# Arduino.net
KiCad netlist of a schematic drawn in Altium Designer
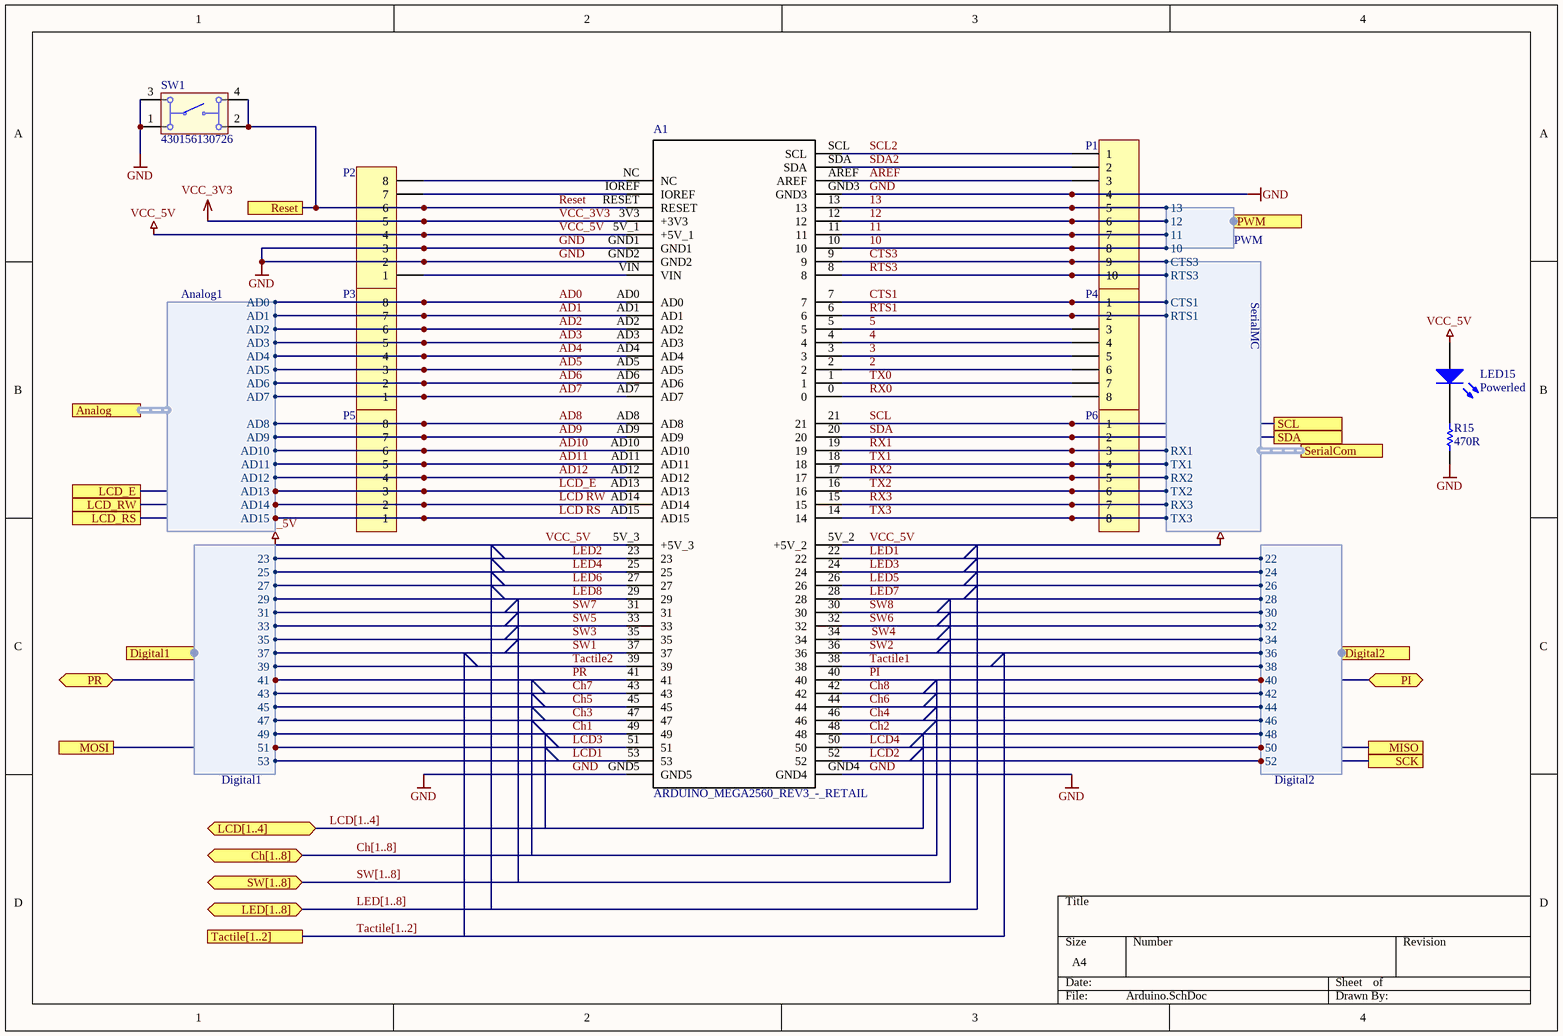
[diagram p0: Arduino.SchDoc]

(export (version "E")
  (design (tool "Eeschema 10.0.6"))
  (components
    (comp (ref "A1")
      (value "ARDUINO_MEGA2560_REV3_-_RETAIL")
      (footprint "*ARDUINO_MEGA2560_REV3_-_RETAIL_ARDUINO_MEGA2560_REV3_-_RETAIL(Primary)")
      (description "Dev.kit: Arduino; SPI, TWI, UART; ICSP, USB B, pin strips, supply")
      (fields (field (name "MF") "Arduino") (field (name "MP") "ARDUINO MEGA2560 REV3 - RETAIL"))
      (libsource (lib "ARDUINO_MEGA2560_REV3_-_RETAIL") (part "ARDUINO_MEGA2560_REV3_-_RETAIL"))
    )
    (comp (ref "LED15")
      (value "Powerled")
      (footprint "1206_A")
      (description "SMD mono-color Chip LED, WL-SMCW, Red")
      (fields (field (name "PARTNUMBER") "150120RS75000") (field (name "MANUFACTURER") "Wuerth Elektronik"))
      (libsource (lib "Altium Content Vault") (part "WE-LED_K1A2-2"))
    )
    (comp (ref "P1")
      (value "Header 10")
      (footprint "HDR1X10")
      (description "Header, 10-Pin")
      (fields (field (name "PUBLISHER") "Altium Limited"))
      (libsource (lib "Miscellaneous Connectors") (part "Header 10"))
    )
    (comp (ref "P2")
      (value "Header 8")
      (footprint "HDR1X8")
      (description "Header, 8-Pin")
      (fields (field (name "PUBLISHER") "Altium Limited"))
      (libsource (lib "") (part "Header 8_1"))
    )
    (comp (ref "P3")
      (value "Header 8")
      (footprint "HDR1X8")
      (description "Header, 8-Pin")
      (fields (field (name "PUBLISHER") "Altium Limited"))
      (libsource (lib "") (part "Header 8_1"))
    )
    (comp (ref "P4")
      (value "Header 8")
      (footprint "HDR1X8")
      (description "Header, 8-Pin")
      (fields (field (name "PUBLISHER") "Altium Limited"))
      (libsource (lib "Miscellaneous Connectors") (part "Header 8"))
    )
    (comp (ref "P5")
      (value "Header 8")
      (footprint "HDR1X8")
      (description "Header, 8-Pin")
      (fields (field (name "PUBLISHER") "Altium Limited"))
      (libsource (lib "") (part "Header 8_1"))
    )
    (comp (ref "P6")
      (value "Header 8")
      (footprint "HDR1X8")
      (description "Header, 8-Pin")
      (fields (field (name "PUBLISHER") "Altium Limited"))
      (libsource (lib "Miscellaneous Connectors") (part "Header 8"))
    )
    (comp (ref "R15")
      (value "470R")
      (footprint "RESC0805(2012)_M")
      (description "470R 0.125W 1% 0805 (2012 Metric)  SMD")
      (fields (field (name "POWER") "0.125 W") (field (name "TOLERANCE") "1 %"))
      (libsource (lib "Altium Content Vault") (part "RES"))
    )
    (comp (ref "SW1")
      (value "430156130726")
      (footprint "430156130726")
      (description "WS-TATV THT Tact Switch 6X6 mm")
      (fields (field (name "MANUFACTURER") "Wuerth Elektronik"))
      (libsource (lib "Altium Content Vault") (part "WE-TACT-SW-4"))
    )
  )
  (nets
    (net (code "6") (name "/2") (class "Default")
      (node (ref "A1") (pin "2") (pinfunction "2_2") (pintype "passive"))
      (node (ref "P4") (pin "6") (pinfunction "6_6") (pintype "passive"))
    )
    (net (code "7") (name "/3") (class "Default")
      (node (ref "A1") (pin "3") (pinfunction "3_3") (pintype "passive"))
      (node (ref "P4") (pin "5") (pinfunction "5_5") (pintype "passive"))
    )
    (net (code "8") (name "/4") (class "Default")
      (node (ref "A1") (pin "4") (pinfunction "4_4") (pintype "passive"))
      (node (ref "P4") (pin "4") (pinfunction "4_4") (pintype "passive"))
    )
    (net (code "9") (name "/5") (class "Default")
      (node (ref "A1") (pin "5") (pinfunction "5_5") (pintype "passive"))
      (node (ref "P4") (pin "3") (pinfunction "3_3") (pintype "passive"))
    )
    (net (code "10") (name "/10") (class "Default")
      (node (ref "A1") (pin "10") (pinfunction "10_10") (pintype "passive"))
      (node (ref "P1") (pin "8") (pinfunction "8_8") (pintype "passive"))
    )
    (net (code "11") (name "/11") (class "Default")
      (node (ref "A1") (pin "11") (pinfunction "11_11") (pintype "passive"))
      (node (ref "P1") (pin "7") (pinfunction "7_7") (pintype "passive"))
    )
    (net (code "12") (name "/12") (class "Default")
      (node (ref "A1") (pin "12") (pinfunction "12_12") (pintype "passive"))
      (node (ref "P1") (pin "6") (pinfunction "6_6") (pintype "passive"))
    )
    (net (code "13") (name "/13") (class "Default")
      (node (ref "A1") (pin "13") (pinfunction "13_13") (pintype "passive"))
      (node (ref "P1") (pin "5") (pinfunction "5_5") (pintype "passive"))
    )
    (net (code "14") (name "/AD0") (class "Default")
      (node (ref "A1") (pin "AD0") (pinfunction "AD0_AD0") (pintype "passive"))
      (node (ref "P3") (pin "8") (pinfunction "8_8") (pintype "passive"))
    )
    (net (code "15") (name "/AD1") (class "Default")
      (node (ref "A1") (pin "AD1") (pinfunction "AD1_AD1") (pintype "passive"))
      (node (ref "P3") (pin "7") (pinfunction "7_7") (pintype "passive"))
    )
    (net (code "16") (name "/AD2") (class "Default")
      (node (ref "A1") (pin "AD2") (pinfunction "AD2_AD2") (pintype "passive"))
      (node (ref "P3") (pin "6") (pinfunction "6_6") (pintype "passive"))
    )
    (net (code "17") (name "/AD3") (class "Default")
      (node (ref "A1") (pin "AD3") (pinfunction "AD3_AD3") (pintype "passive"))
      (node (ref "P3") (pin "5") (pinfunction "5_5") (pintype "passive"))
    )
    (net (code "18") (name "/AD4") (class "Default")
      (node (ref "A1") (pin "AD4") (pinfunction "AD4_AD4") (pintype "passive"))
      (node (ref "P3") (pin "4") (pinfunction "4_4") (pintype "passive"))
    )
    (net (code "19") (name "/AD5") (class "Default")
      (node (ref "A1") (pin "AD5") (pinfunction "AD5_AD5") (pintype "passive"))
      (node (ref "P3") (pin "3") (pinfunction "3_3") (pintype "passive"))
    )
    (net (code "20") (name "/AD6") (class "Default")
      (node (ref "A1") (pin "AD6") (pinfunction "AD6_AD6") (pintype "passive"))
      (node (ref "P3") (pin "2") (pinfunction "2_2") (pintype "passive"))
    )
    (net (code "21") (name "/AD7") (class "Default")
      (node (ref "A1") (pin "AD7") (pinfunction "AD7_AD7") (pintype "passive"))
      (node (ref "P3") (pin "1") (pinfunction "1_1") (pintype "passive"))
    )
    (net (code "22") (name "/AD8") (class "Default")
      (node (ref "A1") (pin "AD8") (pinfunction "AD8_AD8") (pintype "passive"))
      (node (ref "P5") (pin "8") (pinfunction "8_8") (pintype "passive"))
    )
    (net (code "23") (name "/AD9") (class "Default")
      (node (ref "A1") (pin "AD9") (pinfunction "AD9_AD9") (pintype "passive"))
      (node (ref "P5") (pin "7") (pinfunction "7_7") (pintype "passive"))
    )
    (net (code "24") (name "/AD10") (class "Default")
      (node (ref "A1") (pin "AD10") (pinfunction "AD10_AD10") (pintype "passive"))
      (node (ref "P5") (pin "6") (pinfunction "6_6") (pintype "passive"))
    )
    (net (code "25") (name "/AD11") (class "Default")
      (node (ref "A1") (pin "AD11") (pinfunction "AD11_AD11") (pintype "passive"))
      (node (ref "P5") (pin "5") (pinfunction "5_5") (pintype "passive"))
    )
    (net (code "26") (name "/AD12") (class "Default")
      (node (ref "A1") (pin "AD12") (pinfunction "AD12_AD12") (pintype "passive"))
      (node (ref "P5") (pin "4") (pinfunction "4_4") (pintype "passive"))
    )
    (net (code "27") (name "/AREF") (class "Default")
      (node (ref "A1") (pin "AREF") (pinfunction "AREF_AREF") (pintype "passive"))
      (node (ref "P1") (pin "3") (pinfunction "3_3") (pintype "passive"))
    )
    (net (code "28") (name "/CTS1") (class "Default")
      (node (ref "A1") (pin "7") (pinfunction "7_7") (pintype "passive"))
      (node (ref "P4") (pin "1") (pinfunction "1_1") (pintype "passive"))
    )
    (net (code "29") (name "/CTS3") (class "Default")
      (node (ref "A1") (pin "9") (pinfunction "9_9") (pintype "passive"))
      (node (ref "P1") (pin "9") (pinfunction "9_9") (pintype "passive"))
    )
    (net (code "30") (name "/Ch1") (class "Default")
      (node (ref "A1") (pin "49") (pinfunction "49_49") (pintype "passive"))
    )
    (net (code "31") (name "/Ch2") (class "Default")
      (node (ref "A1") (pin "48") (pinfunction "48_48") (pintype "passive"))
    )
    (net (code "32") (name "/Ch3") (class "Default")
      (node (ref "A1") (pin "47") (pinfunction "47_47") (pintype "passive"))
    )
    (net (code "33") (name "/Ch4") (class "Default")
      (node (ref "A1") (pin "46") (pinfunction "46_46") (pintype "passive"))
    )
    (net (code "34") (name "/Ch5") (class "Default")
      (node (ref "A1") (pin "45") (pinfunction "45_45") (pintype "passive"))
    )
    (net (code "35") (name "/Ch6") (class "Default")
      (node (ref "A1") (pin "44") (pinfunction "44_44") (pintype "passive"))
    )
    (net (code "36") (name "/Ch7") (class "Default")
      (node (ref "A1") (pin "43") (pinfunction "43_43") (pintype "passive"))
    )
    (net (code "37") (name "/Ch8") (class "Default")
      (node (ref "A1") (pin "42") (pinfunction "42_42") (pintype "passive"))
    )
    (net (code "39") (name "/LCD RS") (class "Default")
      (node (ref "A1") (pin "AD15") (pinfunction "AD15_AD15") (pintype "passive"))
      (node (ref "P5") (pin "1") (pinfunction "1_1") (pintype "passive"))
    )
    (net (code "40") (name "/LCD RW") (class "Default")
      (node (ref "A1") (pin "AD14") (pinfunction "AD14_AD14") (pintype "passive"))
      (node (ref "P5") (pin "2") (pinfunction "2_2") (pintype "passive"))
    )
    (net (code "41") (name "/LCD1") (class "Default")
      (node (ref "A1") (pin "53") (pinfunction "53_53") (pintype "passive"))
    )
    (net (code "42") (name "/LCD2") (class "Default")
      (node (ref "A1") (pin "52") (pinfunction "52_52") (pintype "passive"))
    )
    (net (code "43") (name "/LCD3") (class "Default")
      (node (ref "A1") (pin "51") (pinfunction "51_51") (pintype "passive"))
    )
    (net (code "44") (name "/LCD4") (class "Default")
      (node (ref "A1") (pin "50") (pinfunction "50_50") (pintype "passive"))
    )
    (net (code "46") (name "/LCD_E") (class "Default")
      (node (ref "A1") (pin "AD13") (pinfunction "AD13_AD13") (pintype "passive"))
      (node (ref "P5") (pin "3") (pinfunction "3_3") (pintype "passive"))
    )
    (net (code "47") (name "/LED1") (class "Default")
      (node (ref "A1") (pin "22") (pinfunction "22_22") (pintype "passive"))
    )
    (net (code "48") (name "/LED2") (class "Default")
      (node (ref "A1") (pin "23") (pinfunction "23_23") (pintype "passive"))
    )
    (net (code "49") (name "/LED3") (class "Default")
      (node (ref "A1") (pin "24") (pinfunction "24_24") (pintype "passive"))
    )
    (net (code "50") (name "/LED4") (class "Default")
      (node (ref "A1") (pin "25") (pinfunction "25_25") (pintype "passive"))
    )
    (net (code "51") (name "/LED5") (class "Default")
      (node (ref "A1") (pin "26") (pinfunction "26_26") (pintype "passive"))
    )
    (net (code "52") (name "/LED6") (class "Default")
      (node (ref "A1") (pin "27") (pinfunction "27_27") (pintype "passive"))
    )
    (net (code "53") (name "/LED7") (class "Default")
      (node (ref "A1") (pin "28") (pinfunction "28_28") (pintype "passive"))
    )
    (net (code "54") (name "/LED8") (class "Default")
      (node (ref "A1") (pin "29") (pinfunction "29_29") (pintype "passive"))
    )
    (net (code "56") (name "/PI") (class "Default")
      (node (ref "A1") (pin "40") (pinfunction "40_40") (pintype "passive"))
    )
    (net (code "57") (name "/PR") (class "Default")
      (node (ref "A1") (pin "41") (pinfunction "41_41") (pintype "passive"))
    )
    (net (code "58") (name "/RTS1") (class "Default")
      (node (ref "A1") (pin "6") (pinfunction "6_6") (pintype "passive"))
      (node (ref "P4") (pin "2") (pinfunction "2_2") (pintype "passive"))
    )
    (net (code "59") (name "/RTS3") (class "Default")
      (node (ref "A1") (pin "8") (pinfunction "8_8") (pintype "passive"))
      (node (ref "P1") (pin "10") (pinfunction "10_10") (pintype "passive"))
    )
    (net (code "60") (name "/RX0") (class "Default")
      (node (ref "A1") (pin "0") (pinfunction "0_0") (pintype "passive"))
      (node (ref "P4") (pin "8") (pinfunction "8_8") (pintype "passive"))
    )
    (net (code "61") (name "/RX1") (class "Default")
      (node (ref "A1") (pin "19") (pinfunction "19_19") (pintype "passive"))
      (node (ref "P6") (pin "3") (pinfunction "3_3") (pintype "passive"))
    )
    (net (code "62") (name "/RX2") (class "Default")
      (node (ref "A1") (pin "17") (pinfunction "17_17") (pintype "passive"))
      (node (ref "P6") (pin "5") (pinfunction "5_5") (pintype "passive"))
    )
    (net (code "63") (name "/RX3") (class "Default")
      (node (ref "A1") (pin "15") (pinfunction "15_15") (pintype "passive"))
      (node (ref "P6") (pin "7") (pinfunction "7_7") (pintype "passive"))
    )
    (net (code "64") (name "/Reset") (class "Default")
      (node (ref "A1") (pin "RESET") (pinfunction "RESET_RESET") (pintype "passive"))
      (node (ref "P2") (pin "6") (pinfunction "6_6") (pintype "passive"))
      (node (ref "SW1") (pin "2") (pinfunction "2_2") (pintype "passive"))
      (node (ref "SW1") (pin "4") (pinfunction "4_4") (pintype "passive"))
    )
    (net (code "65") (name "/SCL") (class "Default")
      (node (ref "A1") (pin "21") (pinfunction "21_21") (pintype "passive"))
      (node (ref "P6") (pin "1") (pinfunction "1_1") (pintype "passive"))
    )
    (net (code "66") (name "/SCL2") (class "Default")
      (node (ref "A1") (pin "SCL") (pinfunction "SCL_SCL") (pintype "passive"))
      (node (ref "P1") (pin "1") (pinfunction "1_1") (pintype "passive"))
    )
    (net (code "67") (name "/SDA") (class "Default")
      (node (ref "A1") (pin "20") (pinfunction "20_20") (pintype "passive"))
      (node (ref "P6") (pin "2") (pinfunction "2_2") (pintype "passive"))
    )
    (net (code "68") (name "/SDA2") (class "Default")
      (node (ref "A1") (pin "SDA") (pinfunction "SDA_SDA") (pintype "passive"))
      (node (ref "P1") (pin "2") (pinfunction "2_2") (pintype "passive"))
    )
    (net (code "69") (name "/SW1") (class "Default")
      (node (ref "A1") (pin "37") (pinfunction "37_37") (pintype "passive"))
    )
    (net (code "70") (name "/SW2") (class "Default")
      (node (ref "A1") (pin "36") (pinfunction "36_36") (pintype "passive"))
    )
    (net (code "71") (name "/SW3") (class "Default")
      (node (ref "A1") (pin "35") (pinfunction "35_35") (pintype "passive"))
    )
    (net (code "72") (name "/SW4") (class "Default")
      (node (ref "A1") (pin "34") (pinfunction "34_34") (pintype "passive"))
    )
    (net (code "73") (name "/SW5") (class "Default")
      (node (ref "A1") (pin "33") (pinfunction "33_33") (pintype "passive"))
    )
    (net (code "74") (name "/SW6") (class "Default")
      (node (ref "A1") (pin "32") (pinfunction "32_32") (pintype "passive"))
    )
    (net (code "75") (name "/SW7") (class "Default")
      (node (ref "A1") (pin "31") (pinfunction "31_31") (pintype "passive"))
    )
    (net (code "76") (name "/SW8") (class "Default")
      (node (ref "A1") (pin "30") (pinfunction "30_30") (pintype "passive"))
    )
    (net (code "78") (name "/TX0") (class "Default")
      (node (ref "A1") (pin "1") (pinfunction "1_1") (pintype "passive"))
      (node (ref "P4") (pin "7") (pinfunction "7_7") (pintype "passive"))
    )
    (net (code "79") (name "/TX1") (class "Default")
      (node (ref "A1") (pin "18") (pinfunction "18_18") (pintype "passive"))
      (node (ref "P6") (pin "4") (pinfunction "4_4") (pintype "passive"))
    )
    (net (code "80") (name "/TX2") (class "Default")
      (node (ref "A1") (pin "16") (pinfunction "16_16") (pintype "passive"))
      (node (ref "P6") (pin "6") (pinfunction "6_6") (pintype "passive"))
    )
    (net (code "81") (name "/TX3") (class "Default")
      (node (ref "A1") (pin "14") (pinfunction "14_14") (pintype "passive"))
      (node (ref "P6") (pin "8") (pinfunction "8_8") (pintype "passive"))
    )
    (net (code "82") (name "/Tactile1") (class "Default")
      (node (ref "A1") (pin "38") (pinfunction "38_38") (pintype "passive"))
    )
    (net (code "83") (name "/Tactile2") (class "Default")
      (node (ref "A1") (pin "39") (pinfunction "39_39") (pintype "passive"))
    )
    (net (code "90") (name "GND") (class "Default")
      (node (ref "A1") (pin "GND1") (pinfunction "GND1_GND1") (pintype "passive"))
      (node (ref "A1") (pin "GND2") (pinfunction "GND2_GND2") (pintype "passive"))
      (node (ref "A1") (pin "GND3") (pinfunction "GND3_GND3") (pintype "passive"))
      (node (ref "A1") (pin "GND4") (pinfunction "GND4_GND4") (pintype "passive"))
      (node (ref "A1") (pin "GND5") (pinfunction "GND5_GND5") (pintype "passive"))
      (node (ref "P1") (pin "4") (pinfunction "4_4") (pintype "passive"))
      (node (ref "P2") (pin "2") (pinfunction "2_2") (pintype "passive"))
      (node (ref "P2") (pin "3") (pinfunction "3_3") (pintype "passive"))
      (node (ref "R15") (pin "1") (pinfunction "1_1") (pintype "passive"))
      (node (ref "SW1") (pin "1") (pinfunction "1_1") (pintype "passive"))
      (node (ref "SW1") (pin "3") (pinfunction "3_3") (pintype "passive"))
    )
    (net (code "91") (name "Net-(A1-PadIOREF)") (class "Default")
      (node (ref "A1") (pin "IOREF") (pinfunction "IOREF_IOREF") (pintype "passive"))
      (node (ref "P2") (pin "7") (pinfunction "7_7") (pintype "passive"))
    )
    (net (code "92") (name "Net-(A1-PadNC)") (class "Default")
      (node (ref "A1") (pin "NC") (pinfunction "NC_NC") (pintype "passive"))
      (node (ref "P2") (pin "8") (pinfunction "8_8") (pintype "passive"))
    )
    (net (code "93") (name "Net-(A1-PadVIN)") (class "Default")
      (node (ref "A1") (pin "VIN") (pinfunction "VIN_VIN") (pintype "passive"))
      (node (ref "P2") (pin "1") (pinfunction "1_1") (pintype "passive"))
    )
    (net (code "94") (name "Net-(LED15-K)") (class "Default")
      (node (ref "LED15") (pin "1") (pinfunction "K_1") (pintype "passive"))
      (node (ref "R15") (pin "2") (pinfunction "2_2") (pintype "passive"))
    )
    (net (code "95") (name "VCC_3V3") (class "Default")
      (node (ref "A1") (pin "3V3") (pinfunction "+3V3_3V3") (pintype "passive"))
      (node (ref "P2") (pin "5") (pinfunction "5_5") (pintype "passive"))
    )
    (net (code "96") (name "VCC_5V") (class "Default")
      (node (ref "A1") (pin "5V_1") (pinfunction "+5V_1_5V_1") (pintype "passive"))
      (node (ref "A1") (pin "5V_2") (pinfunction "+5V_2_5V_2") (pintype "passive"))
      (node (ref "A1") (pin "5V_3") (pinfunction "+5V_3_5V_3") (pintype "passive"))
      (node (ref "LED15") (pin "2") (pinfunction "A_2") (pintype "passive"))
      (node (ref "P2") (pin "4") (pinfunction "4_4") (pintype "passive"))
    )
  )
)
